# line_tracer.net
KiCad netlist of a schematic drawn in EAGLE
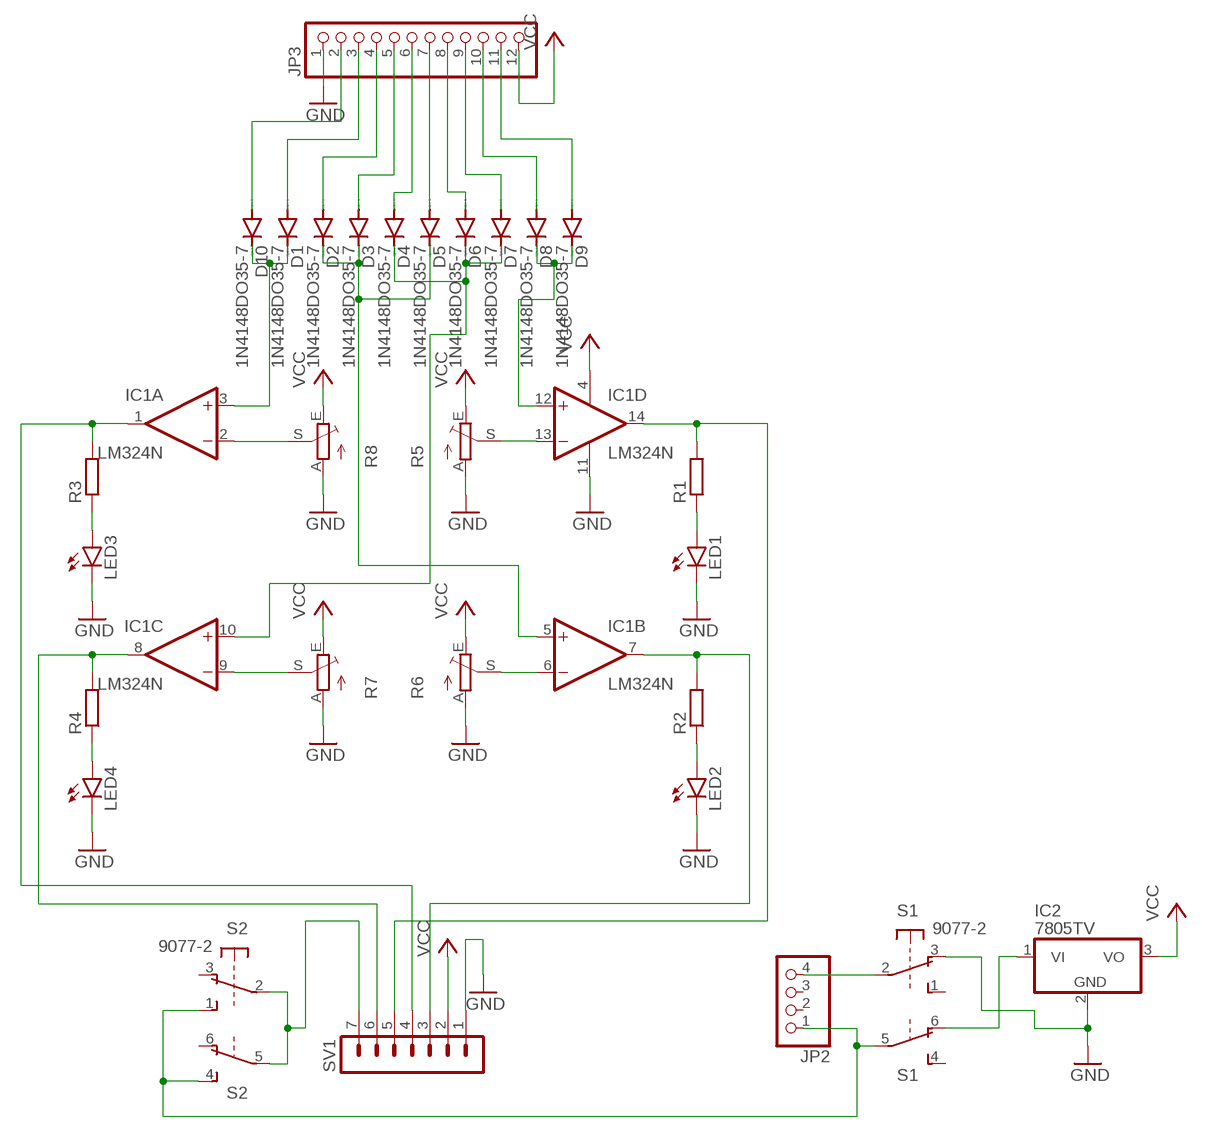
[diagram p0: schematic, sheet 1]

(export (version "E")
  (design (tool "Eeschema 10.0.6"))
  (components
    (comp (ref "D1")
      (value "1N4148DO35-7")
      (footprint "eagle-import:DO35-7")
      (libsource (lib "eagle-import") (part "1N4148DO35-7"))
    )
    (comp (ref "D2")
      (value "1N4148DO35-7")
      (footprint "eagle-import:DO35-7")
      (libsource (lib "eagle-import") (part "1N4148DO35-7"))
    )
    (comp (ref "D3")
      (value "1N4148DO35-7")
      (footprint "eagle-import:DO35-7")
      (libsource (lib "eagle-import") (part "1N4148DO35-7"))
    )
    (comp (ref "D4")
      (value "1N4148DO35-7")
      (footprint "eagle-import:DO35-7")
      (libsource (lib "eagle-import") (part "1N4148DO35-7"))
    )
    (comp (ref "D5")
      (value "1N4148DO35-7")
      (footprint "eagle-import:DO35-7")
      (libsource (lib "eagle-import") (part "1N4148DO35-7"))
    )
    (comp (ref "D6")
      (value "1N4148DO35-7")
      (footprint "eagle-import:DO35-7")
      (libsource (lib "eagle-import") (part "1N4148DO35-7"))
    )
    (comp (ref "D7")
      (value "1N4148DO35-7")
      (footprint "eagle-import:DO35-7")
      (libsource (lib "eagle-import") (part "1N4148DO35-7"))
    )
    (comp (ref "D8")
      (value "1N4148DO35-7")
      (footprint "eagle-import:DO35-7")
      (libsource (lib "eagle-import") (part "1N4148DO35-7"))
    )
    (comp (ref "D9")
      (value "1N4148DO35-7")
      (footprint "eagle-import:DO35-7")
      (libsource (lib "eagle-import") (part "1N4148DO35-7"))
    )
    (comp (ref "D10")
      (value "1N4148DO35-7")
      (footprint "eagle-import:DO35-7")
      (libsource (lib "eagle-import") (part "1N4148DO35-7"))
    )
    (comp (ref "IC1")
      (value "LM324N")
      (footprint "eagle-import:DIL14")
      (libsource (lib "eagle-import") (part "LM324N"))
    )
    (comp (ref "IC2")
      (value "7805TV")
      (footprint "eagle-import:TO220V")
      (libsource (lib "eagle-import") (part "78TV05"))
    )
    (comp (ref "JP2")
      (value "PINHD-1X4")
      (footprint "eagle-import:1X04")
      (libsource (lib "eagle-import") (part "PINHD-1X4"))
    )
    (comp (ref "JP3")
      (value "PINHD-1X12")
      (footprint "eagle-import:1X12")
      (libsource (lib "eagle-import") (part "PINHD-1X12"))
    )
    (comp (ref "LED1")
      (value "LED3MM")
      (footprint "eagle-import:LED3MM")
      (libsource (lib "eagle-import") (part "LED3MM"))
    )
    (comp (ref "LED2")
      (value "LED3MM")
      (footprint "eagle-import:LED3MM")
      (libsource (lib "eagle-import") (part "LED3MM"))
    )
    (comp (ref "LED3")
      (value "LED3MM")
      (footprint "eagle-import:LED3MM")
      (libsource (lib "eagle-import") (part "LED3MM"))
    )
    (comp (ref "LED4")
      (value "LED3MM")
      (footprint "eagle-import:LED3MM")
      (libsource (lib "eagle-import") (part "LED3MM"))
    )
    (comp (ref "R1")
      (value "R-EU_0207/7")
      (footprint "eagle-import:0207_7")
      (libsource (lib "eagle-import") (part "R-EU_0207/7"))
    )
    (comp (ref "R2")
      (value "R-EU_0207/7")
      (footprint "eagle-import:0207_7")
      (libsource (lib "eagle-import") (part "R-EU_0207/7"))
    )
    (comp (ref "R3")
      (value "R-EU_0207/7")
      (footprint "eagle-import:0207_7")
      (libsource (lib "eagle-import") (part "R-EU_0207/7"))
    )
    (comp (ref "R4")
      (value "R-EU_0207/7")
      (footprint "eagle-import:0207_7")
      (libsource (lib "eagle-import") (part "R-EU_0207/7"))
    )
    (comp (ref "R5")
      (value "TRIM_EU-CA6V")
      (footprint "eagle-import:CA6V")
      (libsource (lib "eagle-import") (part "TRIM_EU-CA6V"))
    )
    (comp (ref "R6")
      (value "TRIM_EU-CA6V")
      (footprint "eagle-import:CA6V")
      (libsource (lib "eagle-import") (part "TRIM_EU-CA6V"))
    )
    (comp (ref "R7")
      (value "TRIM_EU-CA6V")
      (footprint "eagle-import:CA6V")
      (libsource (lib "eagle-import") (part "TRIM_EU-CA6V"))
    )
    (comp (ref "R8")
      (value "TRIM_EU-CA6V")
      (footprint "eagle-import:CA6V")
      (libsource (lib "eagle-import") (part "TRIM_EU-CA6V"))
    )
    (comp (ref "S1")
      (value "9077-2")
      (footprint "eagle-import:9077-2")
      (libsource (lib "eagle-import") (part "9077-2"))
    )
    (comp (ref "S2")
      (value "9077-2")
      (footprint "eagle-import:9077-2")
      (libsource (lib "eagle-import") (part "9077-2"))
    )
    (comp (ref "SV1")
      (value "MA07-1")
      (footprint "eagle-import:MA07-1")
      (libsource (lib "eagle-import") (part "MA07-1"))
    )
  )
  (nets
    (net (code "1") (name "GND") (class "Default")
      (node (ref "IC1") (pin "11") (pinfunction "V-_11") (pintype "power_in"))
      (node (ref "IC2") (pin "2") (pinfunction "GND_2") (pintype "passive"))
      (node (ref "JP3") (pin "1") (pinfunction "1_1") (pintype "passive"))
      (node (ref "LED1") (pin "K") (pinfunction "C_K") (pintype "passive"))
      (node (ref "LED2") (pin "K") (pinfunction "C_K") (pintype "passive"))
      (node (ref "LED3") (pin "K") (pinfunction "C_K") (pintype "passive"))
      (node (ref "LED4") (pin "K") (pinfunction "C_K") (pintype "passive"))
      (node (ref "R5") (pin "A") (pinfunction "A_A") (pintype "passive"))
      (node (ref "R6") (pin "A") (pinfunction "A_A") (pintype "passive"))
      (node (ref "R7") (pin "A") (pinfunction "A_A") (pintype "passive"))
      (node (ref "R8") (pin "A") (pinfunction "A_A") (pintype "passive"))
      (node (ref "S1") (pin "3") (pinfunction "O_3") (pintype "passive"))
      (node (ref "SV1") (pin "1") (pinfunction "1_1") (pintype "passive"))
    )
    (net (code "2") (name "Net-(D1-PadA)") (class "Default")
      (node (ref "D1") (pin "A") (pinfunction "A_A") (pintype "passive"))
      (node (ref "JP3") (pin "3") (pinfunction "3_3") (pintype "passive"))
    )
    (net (code "3") (name "Net-(D2-PadA)") (class "Default")
      (node (ref "D2") (pin "A") (pinfunction "A_A") (pintype "passive"))
      (node (ref "JP3") (pin "4") (pinfunction "4_4") (pintype "passive"))
    )
    (net (code "4") (name "Net-(D3-PadA)") (class "Default")
      (node (ref "D3") (pin "A") (pinfunction "A_A") (pintype "passive"))
      (node (ref "JP3") (pin "5") (pinfunction "5_5") (pintype "passive"))
    )
    (net (code "5") (name "Net-(D4-PadA)") (class "Default")
      (node (ref "D4") (pin "A") (pinfunction "A_A") (pintype "passive"))
      (node (ref "JP3") (pin "6") (pinfunction "6_6") (pintype "passive"))
    )
    (net (code "6") (name "Net-(D5-PadA)") (class "Default")
      (node (ref "D5") (pin "A") (pinfunction "A_A") (pintype "passive"))
      (node (ref "JP3") (pin "7") (pinfunction "7_7") (pintype "passive"))
    )
    (net (code "7") (name "Net-(D6-PadA)") (class "Default")
      (node (ref "D6") (pin "A") (pinfunction "A_A") (pintype "passive"))
      (node (ref "JP3") (pin "8") (pinfunction "8_8") (pintype "passive"))
    )
    (net (code "8") (name "Net-(D7-PadA)") (class "Default")
      (node (ref "D7") (pin "A") (pinfunction "A_A") (pintype "passive"))
      (node (ref "JP3") (pin "9") (pinfunction "9_9") (pintype "passive"))
    )
    (net (code "9") (name "Net-(D8-PadA)") (class "Default")
      (node (ref "D8") (pin "A") (pinfunction "A_A") (pintype "passive"))
      (node (ref "JP3") (pin "10") (pinfunction "10_10") (pintype "passive"))
    )
    (net (code "10") (name "Net-(D9-PadA)") (class "Default")
      (node (ref "D9") (pin "A") (pinfunction "A_A") (pintype "passive"))
      (node (ref "JP3") (pin "11") (pinfunction "11_11") (pintype "passive"))
    )
    (net (code "11") (name "Net-(D10-PadA)") (class "Default")
      (node (ref "D10") (pin "A") (pinfunction "A_A") (pintype "passive"))
      (node (ref "JP3") (pin "2") (pinfunction "2_2") (pintype "passive"))
    )
    (net (code "12") (name "Net-(IC1A-+IN)") (class "Default")
      (node (ref "D1") (pin "C") (pinfunction "C_C") (pintype "passive"))
      (node (ref "D10") (pin "C") (pinfunction "C_C") (pintype "passive"))
      (node (ref "IC1") (pin "3") (pinfunction "+IN_3") (pintype "input"))
    )
    (net (code "13") (name "Net-(IC1A--IN)") (class "Default")
      (node (ref "IC1") (pin "2") (pinfunction "-IN_2") (pintype "input"))
      (node (ref "R8") (pin "S") (pinfunction "S_S") (pintype "passive"))
    )
    (net (code "14") (name "Net-(IC1A-OUT)") (class "Default")
      (node (ref "IC1") (pin "1") (pinfunction "OUT_1") (pintype "output"))
      (node (ref "R3") (pin "2") (pinfunction "2_2") (pintype "passive"))
      (node (ref "SV1") (pin "4") (pinfunction "4_4") (pintype "passive"))
    )
    (net (code "15") (name "Net-(IC1B-+IN)") (class "Default")
      (node (ref "D2") (pin "C") (pinfunction "C_C") (pintype "passive"))
      (node (ref "D3") (pin "C") (pinfunction "C_C") (pintype "passive"))
      (node (ref "D5") (pin "C") (pinfunction "C_C") (pintype "passive"))
      (node (ref "IC1") (pin "5") (pinfunction "+IN_5") (pintype "input"))
    )
    (net (code "16") (name "Net-(IC1B--IN)") (class "Default")
      (node (ref "IC1") (pin "6") (pinfunction "-IN_6") (pintype "input"))
      (node (ref "R6") (pin "S") (pinfunction "S_S") (pintype "passive"))
    )
    (net (code "17") (name "Net-(IC1B-OUT)") (class "Default")
      (node (ref "IC1") (pin "7") (pinfunction "OUT_7") (pintype "output"))
      (node (ref "R2") (pin "2") (pinfunction "2_2") (pintype "passive"))
      (node (ref "SV1") (pin "3") (pinfunction "3_3") (pintype "passive"))
    )
    (net (code "18") (name "Net-(IC1C-+IN)") (class "Default")
      (node (ref "D4") (pin "C") (pinfunction "C_C") (pintype "passive"))
      (node (ref "D6") (pin "C") (pinfunction "C_C") (pintype "passive"))
      (node (ref "D7") (pin "C") (pinfunction "C_C") (pintype "passive"))
      (node (ref "IC1") (pin "10") (pinfunction "+IN_10") (pintype "input"))
    )
    (net (code "19") (name "Net-(IC1C--IN)") (class "Default")
      (node (ref "IC1") (pin "9") (pinfunction "-IN_9") (pintype "input"))
      (node (ref "R7") (pin "S") (pinfunction "S_S") (pintype "passive"))
    )
    (net (code "20") (name "Net-(IC1C-OUT)") (class "Default")
      (node (ref "IC1") (pin "8") (pinfunction "OUT_8") (pintype "output"))
      (node (ref "R4") (pin "2") (pinfunction "2_2") (pintype "passive"))
      (node (ref "SV1") (pin "6") (pinfunction "6_6") (pintype "passive"))
    )
    (net (code "21") (name "Net-(IC1D-+IN)") (class "Default")
      (node (ref "D8") (pin "C") (pinfunction "C_C") (pintype "passive"))
      (node (ref "D9") (pin "C") (pinfunction "C_C") (pintype "passive"))
      (node (ref "IC1") (pin "12") (pinfunction "+IN_12") (pintype "input"))
    )
    (net (code "22") (name "Net-(IC1D--IN)") (class "Default")
      (node (ref "IC1") (pin "13") (pinfunction "-IN_13") (pintype "input"))
      (node (ref "R5") (pin "S") (pinfunction "S_S") (pintype "passive"))
    )
    (net (code "23") (name "Net-(IC1D-OUT)") (class "Default")
      (node (ref "IC1") (pin "14") (pinfunction "OUT_14") (pintype "output"))
      (node (ref "R1") (pin "2") (pinfunction "2_2") (pintype "passive"))
      (node (ref "SV1") (pin "5") (pinfunction "5_5") (pintype "passive"))
    )
    (net (code "24") (name "Net-(IC2-VI)") (class "Default")
      (node (ref "IC2") (pin "1") (pinfunction "VI_1") (pintype "input"))
      (node (ref "S1") (pin "6") (pinfunction "O_6") (pintype "passive"))
    )
    (net (code "25") (name "Net-(LED1-PadA)") (class "Default")
      (node (ref "LED1") (pin "A") (pinfunction "A_A") (pintype "passive"))
      (node (ref "R1") (pin "1") (pinfunction "1_1") (pintype "passive"))
    )
    (net (code "26") (name "Net-(LED2-PadA)") (class "Default")
      (node (ref "LED2") (pin "A") (pinfunction "A_A") (pintype "passive"))
      (node (ref "R2") (pin "1") (pinfunction "1_1") (pintype "passive"))
    )
    (net (code "27") (name "Net-(LED3-PadA)") (class "Default")
      (node (ref "LED3") (pin "A") (pinfunction "A_A") (pintype "passive"))
      (node (ref "R3") (pin "1") (pinfunction "1_1") (pintype "passive"))
    )
    (net (code "28") (name "Net-(LED4-PadA)") (class "Default")
      (node (ref "LED4") (pin "A") (pinfunction "A_A") (pintype "passive"))
      (node (ref "R4") (pin "1") (pinfunction "1_1") (pintype "passive"))
    )
    (net (code "29") (name "Net-(S1A-P)") (class "Default")
      (node (ref "JP2") (pin "4") (pinfunction "4_4") (pintype "passive"))
      (node (ref "S1") (pin "2") (pinfunction "P_2") (pintype "passive"))
    )
    (net (code "30") (name "Net-(S1B-P)") (class "Default")
      (node (ref "JP2") (pin "1") (pinfunction "1_1") (pintype "passive"))
      (node (ref "S1") (pin "5") (pinfunction "P_5") (pintype "passive"))
      (node (ref "S2") (pin "1") (pinfunction "S_1") (pintype "passive"))
      (node (ref "S2") (pin "4") (pinfunction "S_4") (pintype "passive"))
    )
    (net (code "31") (name "Net-(S2A-P)") (class "Default")
      (node (ref "S2") (pin "2") (pinfunction "P_2") (pintype "passive"))
      (node (ref "S2") (pin "5") (pinfunction "P_5") (pintype "passive"))
      (node (ref "SV1") (pin "7") (pinfunction "7_7") (pintype "passive"))
    )
    (net (code "32") (name "VCC") (class "Default")
      (node (ref "IC1") (pin "4") (pinfunction "V+_4") (pintype "power_in"))
      (node (ref "IC2") (pin "3") (pinfunction "VO_3") (pintype "passive"))
      (node (ref "JP3") (pin "12") (pinfunction "12_12") (pintype "passive"))
      (node (ref "R5") (pin "E") (pinfunction "E_E") (pintype "passive"))
      (node (ref "R6") (pin "E") (pinfunction "E_E") (pintype "passive"))
      (node (ref "R7") (pin "E") (pinfunction "E_E") (pintype "passive"))
      (node (ref "R8") (pin "E") (pinfunction "E_E") (pintype "passive"))
      (node (ref "SV1") (pin "2") (pinfunction "2_2") (pintype "passive"))
    )
    (net (code "33") (name "unconnected-(JP2-Pad2)") (class "Default")
      (node (ref "JP2") (pin "2") (pinfunction "2_2") (pintype "passive"))
    )
    (net (code "34") (name "unconnected-(JP2-Pad3)") (class "Default")
      (node (ref "JP2") (pin "3") (pinfunction "3_3") (pintype "passive"))
    )
    (net (code "35") (name "unconnected-(S1A-S-Pad1)") (class "Default")
      (node (ref "S1") (pin "1") (pinfunction "S_1") (pintype "passive"))
    )
    (net (code "36") (name "unconnected-(S1B-S-Pad4)") (class "Default")
      (node (ref "S1") (pin "4") (pinfunction "S_4") (pintype "passive"))
    )
    (net (code "37") (name "unconnected-(S2A-O-Pad3)") (class "Default")
      (node (ref "S2") (pin "3") (pinfunction "O_3") (pintype "passive"))
    )
    (net (code "38") (name "unconnected-(S2B-O-Pad6)") (class "Default")
      (node (ref "S2") (pin "6") (pinfunction "O_6") (pintype "passive"))
    )
  )
)
